# mahirAMPLIFER.net
KiCad netlist of a schematic drawn in Altium Designer
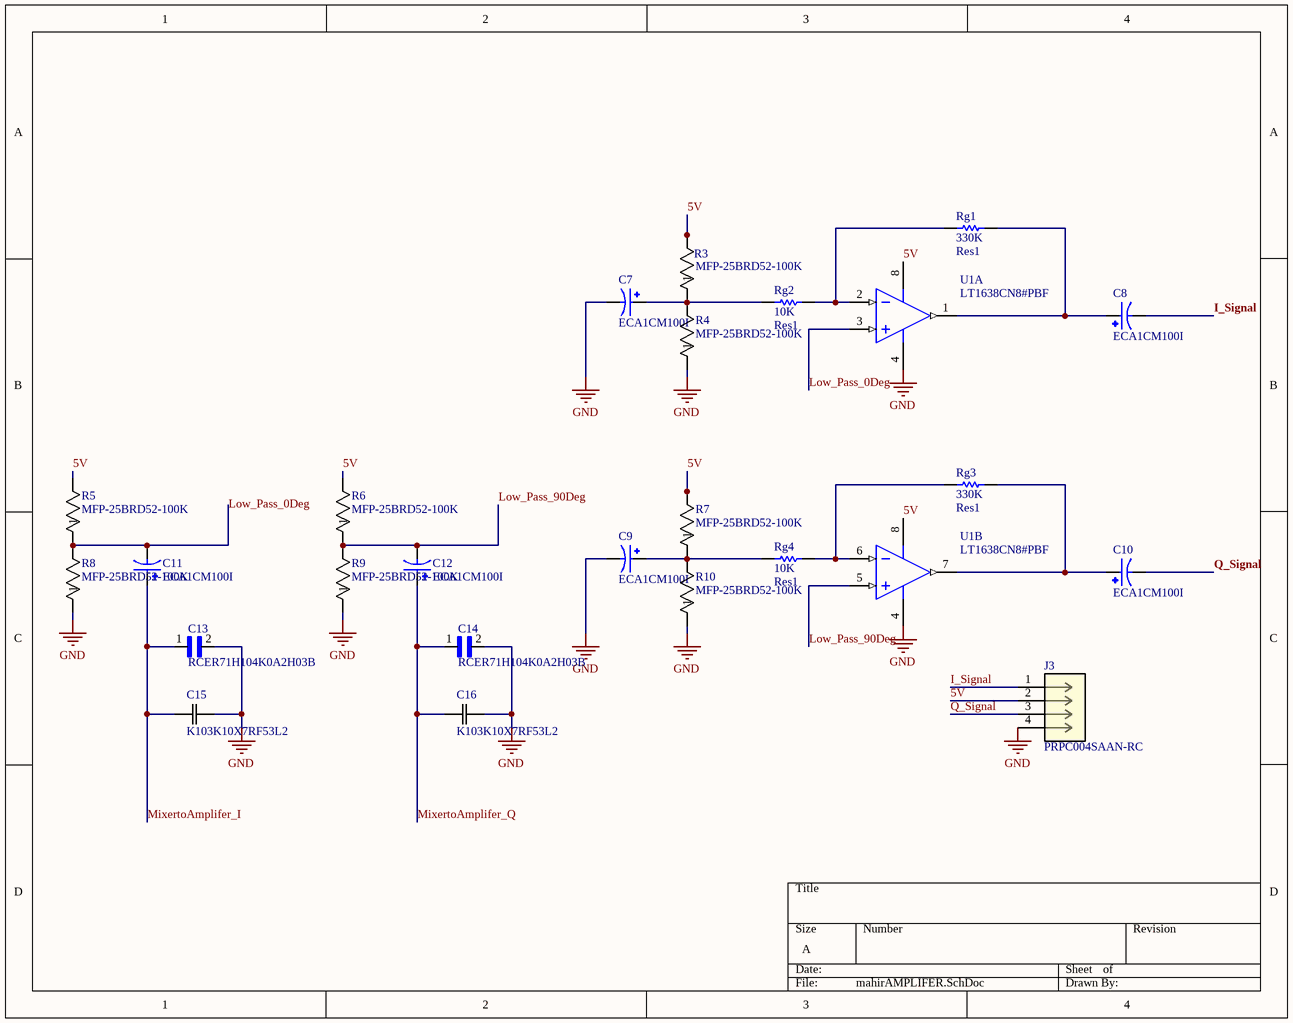
[diagram p0: mahirAMPLIFER.SchDoc]

(export (version "E")
  (design (tool "Eeschema 10.0.6"))
  (components
    (comp (ref "C7")
      (value "ECA1CM100I")
      (footprint "CAPPRD250W50D500H1100")
      (description "10ÂµF 16V Aluminum Electrolytic Capacitors Radial, Can 2000 Hrs @ 85Â°C")
      (fields (field (name "DIGI-KEY_PART_NUMBER") "P19513TB-ND") (field (name "MF") "Panasonic"))
      (libsource (lib "") (part "ECA1CM100I_1"))
    )
    (comp (ref "C8")
      (value "ECA1CM100I")
      (footprint "CAPPRD250W50D500H1100")
      (description "10ÂµF 16V Aluminum Electrolytic Capacitors Radial, Can 2000 Hrs @ 85Â°C")
      (fields (field (name "DIGI-KEY_PART_NUMBER") "P19513TB-ND") (field (name "MF") "Panasonic"))
      (libsource (lib "") (part "ECA1CM100I_2"))
    )
    (comp (ref "C9")
      (value "ECA1CM100I")
      (footprint "CAPPRD250W50D500H1100")
      (description "10ÂµF 16V Aluminum Electrolytic Capacitors Radial, Can 2000 Hrs @ 85Â°C")
      (fields (field (name "DIGI-KEY_PART_NUMBER") "P19513TB-ND") (field (name "MF") "Panasonic"))
      (libsource (lib "") (part "ECA1CM100I_1"))
    )
    (comp (ref "C10")
      (value "ECA1CM100I")
      (footprint "CAPPRD250W50D500H1100")
      (description "10ÂµF 16V Aluminum Electrolytic Capacitors Radial, Can 2000 Hrs @ 85Â°C")
      (fields (field (name "DIGI-KEY_PART_NUMBER") "P19513TB-ND") (field (name "MF") "Panasonic"))
      (libsource (lib "") (part "ECA1CM100I_2"))
    )
    (comp (ref "C11")
      (value "ECA1CM100I")
      (footprint "CAPPRD250W50D500H1100")
      (description "10ÂµF 16V Aluminum Electrolytic Capacitors Radial, Can 2000 Hrs @ 85Â°C")
      (fields (field (name "DIGI-KEY_PART_NUMBER") "P19513TB-ND") (field (name "MF") "Panasonic"))
      (libsource (lib "ECA1CM100I") (part "ECA1CM100I"))
    )
    (comp (ref "C12")
      (value "ECA1CM100I")
      (footprint "CAPPRD250W50D500H1100")
      (description "10ÂµF 16V Aluminum Electrolytic Capacitors Radial, Can 2000 Hrs @ 85Â°C")
      (fields (field (name "DIGI-KEY_PART_NUMBER") "P19513TB-ND") (field (name "MF") "Panasonic"))
      (libsource (lib "ECA1CM100I") (part "ECA1CM100I"))
    )
    (comp (ref "C13")
      (value "RCER71H104K0A2H03B")
      (footprint "CAP_RCER71H104K0A2H03B")
      (description "Cap Ceramic 1pF 50V C0G 0.25pF Radial 2.5mm 125C Automotive Bulk")
      (libsource (lib "RCER71H104K0A2H03B") (part "RCER71H104K0A2H03B"))
    )
    (comp (ref "C14")
      (value "RCER71H104K0A2H03B")
      (footprint "CAP_RCER71H104K0A2H03B")
      (description "Cap Ceramic 1pF 50V C0G 0.25pF Radial 2.5mm 125C Automotive Bulk")
      (libsource (lib "RCER71H104K0A2H03B") (part "RCER71H104K0A2H03B"))
    )
    (comp (ref "C15")
      (value "K103K10X7RF53L2")
      (footprint "K103K10X7RF53L2_VIS")
      (description "No Description Available")
      (libsource (lib "K103K10X7RF53L2") (part "K103K10X7RF53L2"))
    )
    (comp (ref "C16")
      (value "K103K10X7RF53L2")
      (footprint "K103K10X7RF53L2_VIS")
      (description "No Description Available")
      (libsource (lib "K103K10X7RF53L2") (part "K103K10X7RF53L2"))
    )
    (comp (ref "J3")
      (value "PRPC004SAAN-RC")
      (footprint "CONN4_PRPC004_SUL")
      (description "No Description Available")
      (libsource (lib "PRPC004SAAN-RC") (part "PRPC004SAAN-RC"))
    )
    (comp (ref "R3")
      (value "MFP-25BRD52-100K")
      (footprint "YAG_MF25_YAG")
      (description "No Description Available")
      (libsource (lib "MFP-25BRD52-100K") (part "MFP-25BRD52-100K"))
    )
    (comp (ref "R4")
      (value "MFP-25BRD52-100K")
      (footprint "YAG_MF25_YAG")
      (description "No Description Available")
      (libsource (lib "MFP-25BRD52-100K") (part "MFP-25BRD52-100K"))
    )
    (comp (ref "R5")
      (value "MFP-25BRD52-100K")
      (footprint "YAG_MF25_YAG")
      (description "No Description Available")
      (libsource (lib "MFP-25BRD52-100K") (part "MFP-25BRD52-100K"))
    )
    (comp (ref "R6")
      (value "MFP-25BRD52-100K")
      (footprint "YAG_MF25_YAG")
      (description "No Description Available")
      (libsource (lib "MFP-25BRD52-100K") (part "MFP-25BRD52-100K"))
    )
    (comp (ref "R7")
      (value "MFP-25BRD52-100K")
      (footprint "YAG_MF25_YAG")
      (description "No Description Available")
      (libsource (lib "MFP-25BRD52-100K") (part "MFP-25BRD52-100K"))
    )
    (comp (ref "R8")
      (value "MFP-25BRD52-100K")
      (footprint "YAG_MF25_YAG")
      (description "No Description Available")
      (libsource (lib "MFP-25BRD52-100K") (part "MFP-25BRD52-100K"))
    )
    (comp (ref "R9")
      (value "MFP-25BRD52-100K")
      (footprint "YAG_MF25_YAG")
      (description "No Description Available")
      (libsource (lib "MFP-25BRD52-100K") (part "MFP-25BRD52-100K"))
    )
    (comp (ref "R10")
      (value "MFP-25BRD52-100K")
      (footprint "YAG_MF25_YAG")
      (description "No Description Available")
      (libsource (lib "MFP-25BRD52-100K") (part "MFP-25BRD52-100K"))
    )
    (comp (ref "Rg1")
      (value "Res1")
      (footprint "AXIAL-0.1-RES")
      (description "Resistor")
      (fields
        (field (name "ALTIUM_VALUE") "330K")
        (field (name "MANUFACTURER PART NUMBER") "CFR-25JB-52-330K")
        (field (name "TOLERANCE") "0.05")
        (field (name "PUBLISHER") "Altium Limited")
      )
      (libsource (lib "ECE295-Resistors-TH") (part "RES 330K OHM 5% 1/4W AXIAL"))
    )
    (comp (ref "Rg2")
      (value "Res1")
      (footprint "AXIAL-0.1-RES")
      (description "Resistor")
      (fields
        (field (name "ALTIUM_VALUE") "10K")
        (field (name "MANUFACTURER PART NUMBER") "CFR-25JB-52-10K")
        (field (name "TOLERANCE") "0.05")
        (field (name "PUBLISHER") "Altium Limited")
      )
      (libsource (lib "ECE295-Resistors-TH") (part "RES 10K OHM 5% 1/4W AXIAL"))
    )
    (comp (ref "Rg3")
      (value "Res1")
      (footprint "AXIAL-0.1-RES")
      (description "Resistor")
      (fields
        (field (name "ALTIUM_VALUE") "330K")
        (field (name "MANUFACTURER PART NUMBER") "CFR-25JB-52-330K")
        (field (name "TOLERANCE") "0.05")
        (field (name "PUBLISHER") "Altium Limited")
      )
      (libsource (lib "ECE295-Resistors-TH") (part "RES 330K OHM 5% 1/4W AXIAL"))
    )
    (comp (ref "Rg4")
      (value "Res1")
      (footprint "AXIAL-0.1-RES")
      (description "Resistor")
      (fields
        (field (name "ALTIUM_VALUE") "10K")
        (field (name "MANUFACTURER PART NUMBER") "CFR-25JB-52-10K")
        (field (name "TOLERANCE") "0.05")
        (field (name "PUBLISHER") "Altium Limited")
      )
      (libsource (lib "ECE295-Resistors-TH") (part "RES 10K OHM 5% 1/4W AXIAL"))
    )
    (comp (ref "U1")
      (value "LT1638CN8#PBF")
      (footprint "LT-N8-8")
      (fields
        (field (name "MANUFACTURER") "Linear Technology")
        (field (name "LINEAR TECHNOLOGY PART NUMBER") "LT1638")
      )
      (libsource (lib "Altium Content Vault") (part "LT-LT1638-N8-8"))
    )
  )
  (nets
    (net (code "1") (name "/5V") (class "Default")
      (node (ref "J3") (pin "2") (pinfunction "2_2") (pintype "passive"))
      (node (ref "R3") (pin "2") (pinfunction "2_2") (pintype "passive"))
      (node (ref "R5") (pin "2") (pinfunction "2_2") (pintype "passive"))
      (node (ref "R6") (pin "2") (pinfunction "2_2") (pintype "passive"))
      (node (ref "R7") (pin "2") (pinfunction "2_2") (pintype "passive"))
      (node (ref "U1") (pin "8") (pinfunction "V+_8") (pintype "power_in"))
    )
    (net (code "2") (name "/I_Signal") (class "Default")
      (node (ref "C8") (pin "N") (pinfunction "N_N") (pintype "passive"))
      (node (ref "J3") (pin "1") (pinfunction "1_1") (pintype "passive"))
    )
    (net (code "3") (name "/Low_Pass_0Deg") (class "Default")
      (node (ref "C11") (pin "N") (pinfunction "N_N") (pintype "passive"))
      (node (ref "R5") (pin "1") (pinfunction "1_1") (pintype "passive"))
      (node (ref "R8") (pin "2") (pinfunction "2_2") (pintype "passive"))
      (node (ref "U1") (pin "3") (pinfunction "+IN_A_3") (pintype "input"))
    )
    (net (code "4") (name "/Low_Pass_90Deg") (class "Default")
      (node (ref "C12") (pin "N") (pinfunction "N_N") (pintype "passive"))
      (node (ref "R6") (pin "1") (pinfunction "1_1") (pintype "passive"))
      (node (ref "R9") (pin "2") (pinfunction "2_2") (pintype "passive"))
      (node (ref "U1") (pin "5") (pinfunction "+IN_B_5") (pintype "input"))
    )
    (net (code "5") (name "/MixertoAmplifer_I") (class "Default")
      (node (ref "C11") (pin "P") (pinfunction "P_P") (pintype "passive"))
      (node (ref "C13") (pin "1") (pinfunction "1_1") (pintype "passive"))
      (node (ref "C15") (pin "1") (pinfunction "1_1") (pintype "passive"))
    )
    (net (code "6") (name "/MixertoAmplifer_Q") (class "Default")
      (node (ref "C12") (pin "P") (pinfunction "P_P") (pintype "passive"))
      (node (ref "C14") (pin "1") (pinfunction "1_1") (pintype "passive"))
      (node (ref "C16") (pin "1") (pinfunction "1_1") (pintype "passive"))
    )
    (net (code "7") (name "/Q_Signal") (class "Default")
      (node (ref "C10") (pin "N") (pinfunction "N_N") (pintype "passive"))
      (node (ref "J3") (pin "3") (pinfunction "3_3") (pintype "passive"))
    )
    (net (code "8") (name "GND") (class "Default")
      (node (ref "C13") (pin "2") (pinfunction "2_2") (pintype "passive"))
      (node (ref "C14") (pin "2") (pinfunction "2_2") (pintype "passive"))
      (node (ref "C15") (pin "2") (pinfunction "2_2") (pintype "passive"))
      (node (ref "C16") (pin "2") (pinfunction "2_2") (pintype "passive"))
      (node (ref "C7") (pin "N") (pinfunction "N_N") (pintype "passive"))
      (node (ref "C9") (pin "N") (pinfunction "N_N") (pintype "passive"))
      (node (ref "J3") (pin "4") (pinfunction "4_4") (pintype "passive"))
      (node (ref "R10") (pin "1") (pinfunction "1_1") (pintype "passive"))
      (node (ref "R4") (pin "1") (pinfunction "1_1") (pintype "passive"))
      (node (ref "R8") (pin "1") (pinfunction "1_1") (pintype "passive"))
      (node (ref "R9") (pin "1") (pinfunction "1_1") (pintype "passive"))
      (node (ref "U1") (pin "4") (pinfunction "V-_4") (pintype "power_in"))
    )
    (net (code "9") (name "Net-(C7-PadP)") (class "Default")
      (node (ref "C7") (pin "P") (pinfunction "P_P") (pintype "passive"))
      (node (ref "R3") (pin "1") (pinfunction "1_1") (pintype "passive"))
      (node (ref "R4") (pin "2") (pinfunction "2_2") (pintype "passive"))
      (node (ref "Rg2") (pin "1") (pinfunction "1_1") (pintype "passive"))
    )
    (net (code "10") (name "Net-(C9-PadP)") (class "Default")
      (node (ref "C9") (pin "P") (pinfunction "P_P") (pintype "passive"))
      (node (ref "R10") (pin "2") (pinfunction "2_2") (pintype "passive"))
      (node (ref "R7") (pin "1") (pinfunction "1_1") (pintype "passive"))
      (node (ref "Rg4") (pin "1") (pinfunction "1_1") (pintype "passive"))
    )
    (net (code "11") (name "Net-(U1A--IN_A)") (class "Default")
      (node (ref "Rg1") (pin "1") (pinfunction "1_1") (pintype "passive"))
      (node (ref "Rg2") (pin "2") (pinfunction "2_2") (pintype "passive"))
      (node (ref "U1") (pin "2") (pinfunction "-IN_A_2") (pintype "input"))
    )
    (net (code "12") (name "Net-(U1A-OUT_A)") (class "Default")
      (node (ref "C8") (pin "P") (pinfunction "P_P") (pintype "passive"))
      (node (ref "Rg1") (pin "2") (pinfunction "2_2") (pintype "passive"))
      (node (ref "U1") (pin "1") (pinfunction "OUT_A_1") (pintype "output"))
    )
    (net (code "13") (name "Net-(U1B--IN_B)") (class "Default")
      (node (ref "Rg3") (pin "1") (pinfunction "1_1") (pintype "passive"))
      (node (ref "Rg4") (pin "2") (pinfunction "2_2") (pintype "passive"))
      (node (ref "U1") (pin "6") (pinfunction "-IN_B_6") (pintype "input"))
    )
    (net (code "14") (name "Net-(U1B-OUT_B)") (class "Default")
      (node (ref "C10") (pin "P") (pinfunction "P_P") (pintype "passive"))
      (node (ref "Rg3") (pin "2") (pinfunction "2_2") (pintype "passive"))
      (node (ref "U1") (pin "7") (pinfunction "OUT_B_7") (pintype "output"))
    )
  )
)
